# Schematic.net
KiCad netlist of a schematic drawn in EAGLE
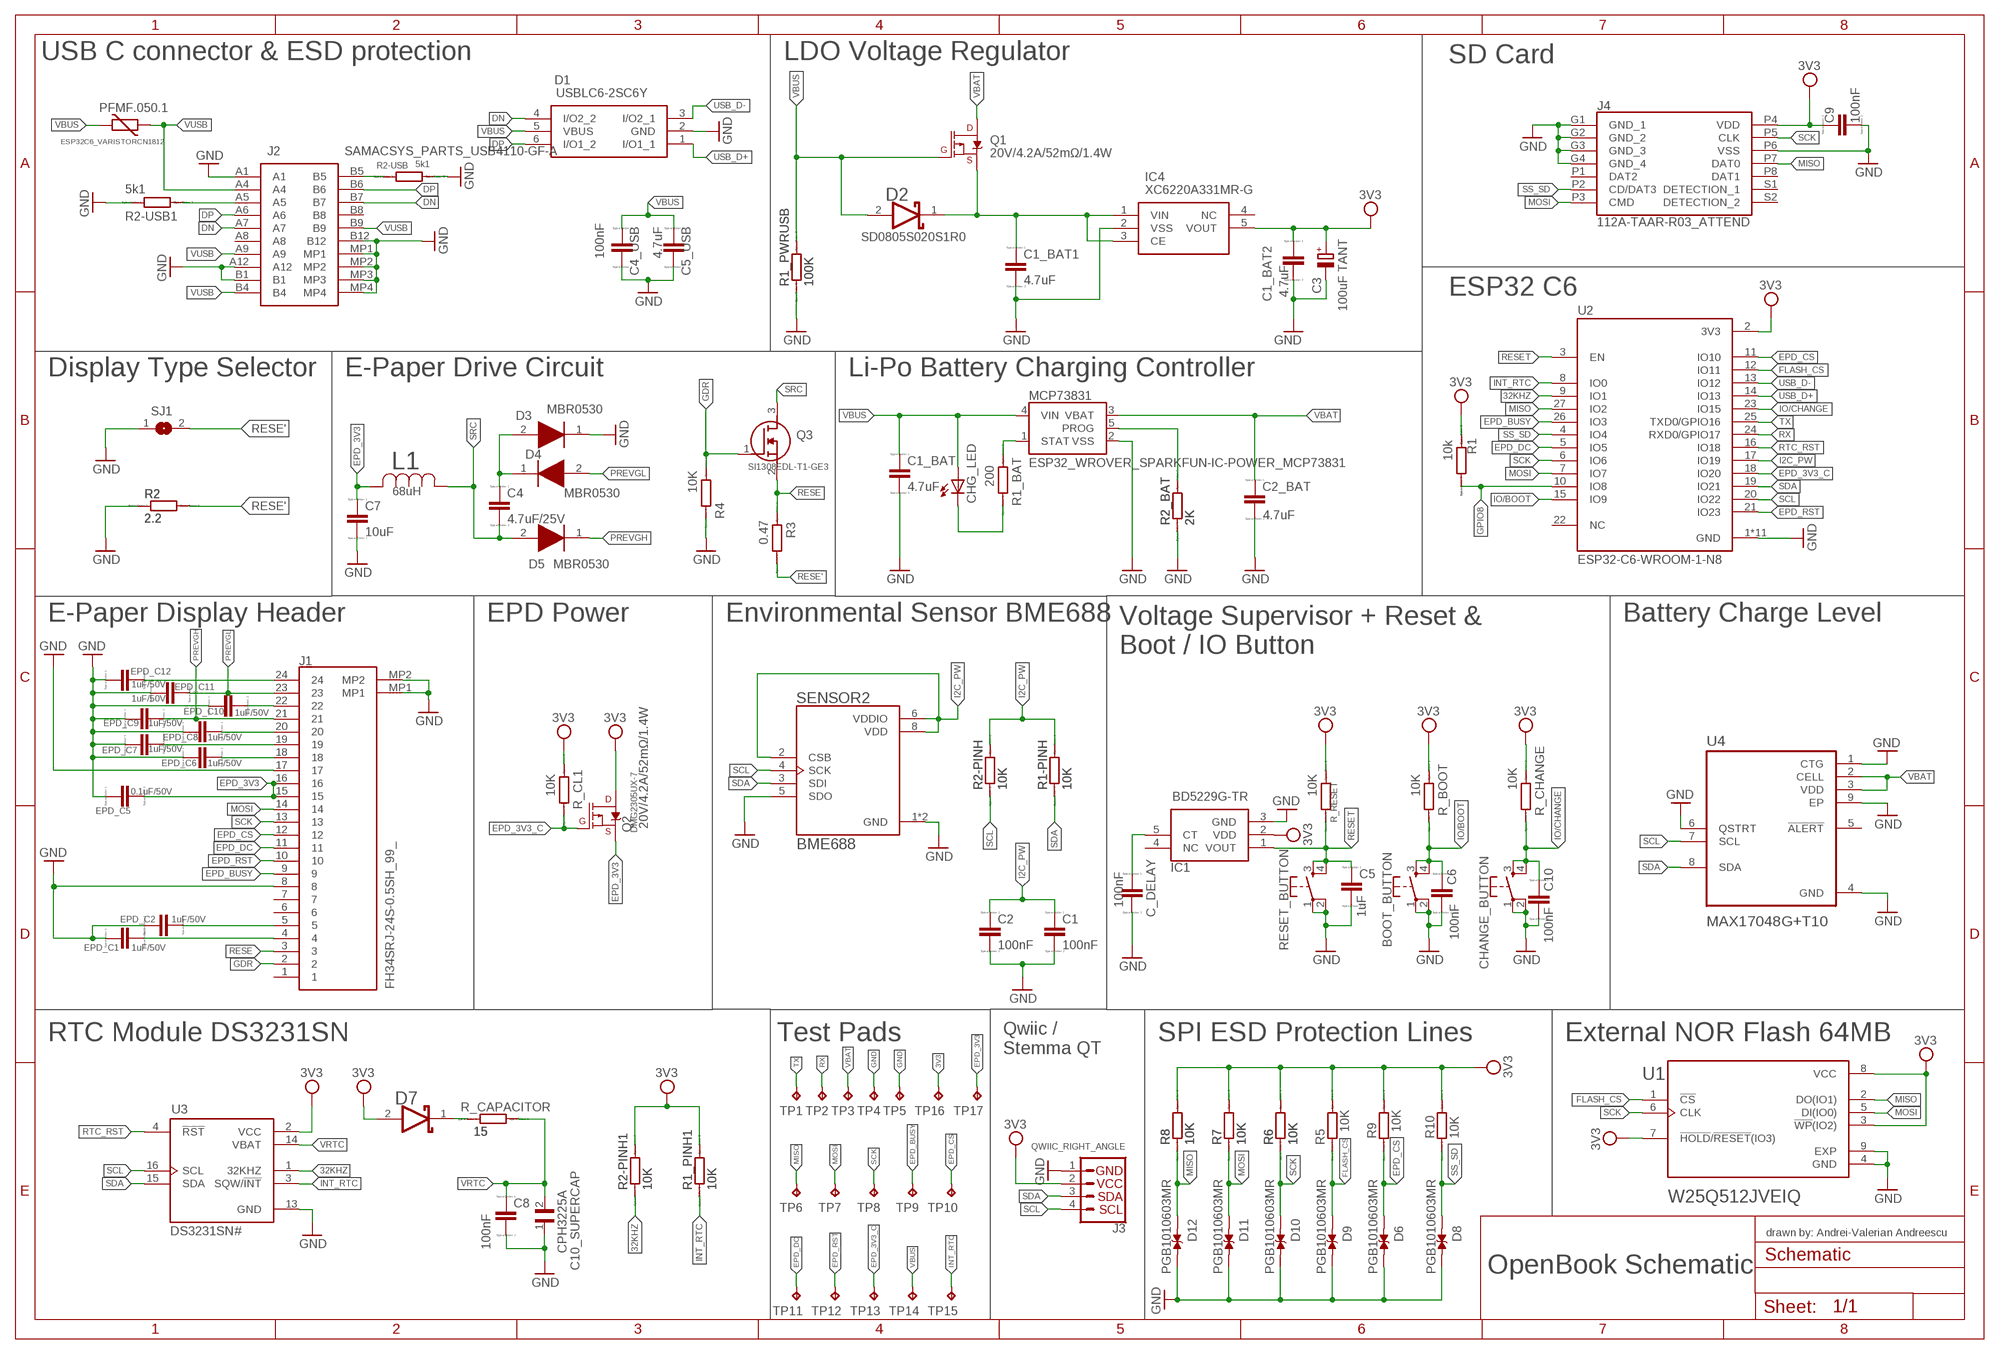
[diagram p0: schematic, sheet 1]

(export (version "E")
  (design (tool "Eeschema 10.0.6"))
  (components
    (comp (ref "BOOT_BUTTON")
      (value "BUTTON_CUSYOMV1")
      (footprint "eagle-import:MYBUTTON")
      (libsource (lib "eagle-import") (part "BUTTON_CUSYOMV1"))
    )
    (comp (ref "C1")
      (value "100nF")
      (footprint "eagle-import:ESP32_WROVER_EAGLE-LTSPICE_C0402")
      (libsource (lib "eagle-import") (part "ESP32_WROVER_EAGLE-LTSPICE_CC0402"))
    )
    (comp (ref "C1_BAT")
      (value "4.7uF")
      (footprint "eagle-import:EAGLE-LTSPICE_C0402")
      (libsource (lib "eagle-import") (part "EAGLE-LTSPICE_CC0402"))
    )
    (comp (ref "C1_BAT1")
      (value "4.7uF")
      (footprint "eagle-import:EAGLE-LTSPICE_C0402")
      (libsource (lib "eagle-import") (part "EAGLE-LTSPICE_CC0402"))
    )
    (comp (ref "C1_BAT2")
      (value "4.7uF")
      (footprint "eagle-import:EAGLE-LTSPICE_C0402")
      (libsource (lib "eagle-import") (part "EAGLE-LTSPICE_CC0402"))
    )
    (comp (ref "C2")
      (value "100nF")
      (footprint "eagle-import:ESP32_WROVER_EAGLE-LTSPICE_C0402")
      (libsource (lib "eagle-import") (part "ESP32_WROVER_EAGLE-LTSPICE_CC0402"))
    )
    (comp (ref "C2_BAT")
      (value "4.7uF")
      (footprint "eagle-import:EAGLE-LTSPICE_C0402")
      (libsource (lib "eagle-import") (part "EAGLE-LTSPICE_CC0402"))
    )
    (comp (ref "C3")
      (value "100uF TANT")
      (footprint "eagle-import:RCL_CT3528")
      (libsource (lib "eagle-import") (part "RCL_CPOL-EUCT3528"))
    )
    (comp (ref "C4")
      (value "4.7uF/25V")
      (footprint "eagle-import:ESP32_WROVER_EAGLE-LTSPICE_C0402")
      (libsource (lib "eagle-import") (part "ESP32_WROVER_EAGLE-LTSPICE_CC0402"))
    )
    (comp (ref "C4_USB")
      (value "100nF")
      (footprint "eagle-import:EAGLE-LTSPICE_C0402")
      (libsource (lib "eagle-import") (part "EAGLE-LTSPICE_CC0402"))
    )
    (comp (ref "C5")
      (value "1uF")
      (footprint "eagle-import:ESP32_WROVER_EAGLE-LTSPICE_C0402")
      (libsource (lib "eagle-import") (part "ESP32_WROVER_EAGLE-LTSPICE_CC0402"))
    )
    (comp (ref "C5_USB")
      (value "4.7uF")
      (footprint "eagle-import:EAGLE-LTSPICE_C0402")
      (libsource (lib "eagle-import") (part "EAGLE-LTSPICE_CC0402"))
    )
    (comp (ref "C6")
      (value "100nF")
      (footprint "eagle-import:ESP32_WROVER_EAGLE-LTSPICE_C0402")
      (libsource (lib "eagle-import") (part "ESP32_WROVER_EAGLE-LTSPICE_CC0402"))
    )
    (comp (ref "C7")
      (value "10uF")
      (footprint "eagle-import:ESP32_WROVER_EAGLE-LTSPICE_C0402")
      (libsource (lib "eagle-import") (part "ESP32_WROVER_EAGLE-LTSPICE_CC0402"))
    )
    (comp (ref "C8")
      (value "100nF")
      (footprint "eagle-import:ESP32_WROVER_EAGLE-LTSPICE_C0402")
      (libsource (lib "eagle-import") (part "ESP32_WROVER_EAGLE-LTSPICE_CC0402"))
    )
    (comp (ref "C9")
      (value "100nF")
      (footprint "eagle-import:EAGLE-LTSPICE_C0402")
      (libsource (lib "eagle-import") (part "EAGLE-LTSPICE_CC0402"))
    )
    (comp (ref "C10")
      (value "100nF")
      (footprint "eagle-import:ESP32_WROVER_EAGLE-LTSPICE_C0402")
      (libsource (lib "eagle-import") (part "ESP32_WROVER_EAGLE-LTSPICE_CC0402"))
    )
    (comp (ref "C10_SUPERCAP")
      (value "CPH3225A")
      (footprint "eagle-import:CAPCP3225X100N")
      (fields (field (name "MF") "Seiko Instruments"))
      (libsource (lib "eagle-import") (part "CPH3225A"))
    )
    (comp (ref "CHANGE_BUTTON")
      (value "BUTTON_CUSYOMV1")
      (footprint "eagle-import:MYBUTTON")
      (libsource (lib "eagle-import") (part "BUTTON_CUSYOMV1"))
    )
    (comp (ref "CHG_LED")
      (value "ADAFRUIT_LEDCHIP-LED0603")
      (footprint "eagle-import:ADAFRUIT_CHIP-LED0603")
      (libsource (lib "eagle-import") (part "ADAFRUIT_LEDCHIP-LED0603"))
    )
    (comp (ref "C_DELAY")
      (value "100nF")
      (footprint "eagle-import:ESP32_WROVER_EAGLE-LTSPICE_C0402")
      (libsource (lib "eagle-import") (part "ESP32_WROVER_EAGLE-LTSPICE_CC0402"))
    )
    (comp (ref "D1")
      (value "USBLC6-2SC6Y")
      (footprint "eagle-import:SOIC127P1032X265-16N")
      (fields (field (name "MF") "STMicroelectronics"))
      (libsource (lib "eagle-import") (part "USBLC6-2SC6Y"))
    )
    (comp (ref "D2")
      (value "SD0805S020S1R0")
      (footprint "eagle-import:ESP32_WROVER_AVX---SD0805S020S1R0_AVX_SD0805S020S1R0_0")
      (fields
        (field (name "DIGIKEY_PART_NUMBER") "478-7800-1-ND")
        (field (name "MF") "AVX")
        (field (name "MOUSER_PART_NUMBER") "581-SD0805S020S1R0")
        (field (name "VALUE_DISPLAY") "SD0805S020S1R0")
      )
      (libsource (lib "eagle-import") (part "ESP32_WROVER_AVX---SD0805S020S1R0_AVX_SD0805S020S1R0_0_0AVX_SD0805S020S1R0_0_0"))
    )
    (comp (ref "D3")
      (value "MBR0530")
      (footprint "eagle-import:SOD3716X135N")
      (fields (field (name "MF") "ON Semiconductor"))
      (libsource (lib "eagle-import") (part "MBR0530"))
    )
    (comp (ref "D4")
      (value "MBR0530")
      (footprint "eagle-import:SOD3716X135N")
      (fields (field (name "MF") "ON Semiconductor"))
      (libsource (lib "eagle-import") (part "MBR0530"))
    )
    (comp (ref "D5")
      (value "MBR0530")
      (footprint "eagle-import:SOD3716X135N")
      (fields (field (name "MF") "ON Semiconductor"))
      (libsource (lib "eagle-import") (part "MBR0530"))
    )
    (comp (ref "D6")
      (value "PGB1010603MR")
      (footprint "eagle-import:DIOC1608X36N")
      (fields (field (name "MF") "Littelfuse Inc."))
      (libsource (lib "eagle-import") (part "PGB1010603MR"))
    )
    (comp (ref "D7")
      (value "ESP32_WROVER_AVX---SD0805S020S1R0_AVX_SD0805S020S1R0_0_0AVX_SD0805S020S1R0_0_0")
      (footprint "eagle-import:ESP32_WROVER_AVX---SD0805S020S1R0_AVX_SD0805S020S1R0_0")
      (fields
        (field (name "DIGIKEY_PART_NUMBER") "478-7800-1-ND")
        (field (name "MF") "AVX")
        (field (name "MOUSER_PART_NUMBER") "581-SD0805S020S1R0")
      )
      (libsource (lib "eagle-import") (part "ESP32_WROVER_AVX---SD0805S020S1R0_AVX_SD0805S020S1R0_0_0AVX_SD0805S020S1R0_0_0"))
    )
    (comp (ref "D8")
      (value "PGB1010603MR")
      (footprint "eagle-import:DIOC1608X36N")
      (fields (field (name "MF") "Littelfuse Inc."))
      (libsource (lib "eagle-import") (part "PGB1010603MR"))
    )
    (comp (ref "D9")
      (value "PGB1010603MR")
      (footprint "eagle-import:DIOC1608X36N")
      (fields (field (name "MF") "Littelfuse Inc."))
      (libsource (lib "eagle-import") (part "PGB1010603MR"))
    )
    (comp (ref "D10")
      (value "PGB1010603MR")
      (footprint "eagle-import:DIOC1608X36N")
      (fields (field (name "MF") "Littelfuse Inc."))
      (libsource (lib "eagle-import") (part "PGB1010603MR"))
    )
    (comp (ref "D11")
      (value "PGB1010603MR")
      (footprint "eagle-import:DIOC1608X36N")
      (fields (field (name "MF") "Littelfuse Inc."))
      (libsource (lib "eagle-import") (part "PGB1010603MR"))
    )
    (comp (ref "D12")
      (value "PGB1010603MR")
      (footprint "eagle-import:DIOC1608X36N")
      (fields (field (name "MF") "Littelfuse Inc."))
      (libsource (lib "eagle-import") (part "PGB1010603MR"))
    )
    (comp (ref "EPD_C1")
      (value "1uF/50V")
      (footprint "eagle-import:ESP32_WROVER_EAGLE-LTSPICE_C0402")
      (libsource (lib "eagle-import") (part "ESP32_WROVER_EAGLE-LTSPICE_CC0402"))
    )
    (comp (ref "EPD_C2")
      (value "1uF/50V")
      (footprint "eagle-import:ESP32_WROVER_EAGLE-LTSPICE_C0402")
      (libsource (lib "eagle-import") (part "ESP32_WROVER_EAGLE-LTSPICE_CC0402"))
    )
    (comp (ref "EPD_C5")
      (value "0.1uF/50V")
      (footprint "eagle-import:ESP32_WROVER_EAGLE-LTSPICE_C0402")
      (libsource (lib "eagle-import") (part "ESP32_WROVER_EAGLE-LTSPICE_CC0402"))
    )
    (comp (ref "EPD_C6")
      (value "1uF/50V")
      (footprint "eagle-import:ESP32_WROVER_EAGLE-LTSPICE_C0402")
      (libsource (lib "eagle-import") (part "ESP32_WROVER_EAGLE-LTSPICE_CC0402"))
    )
    (comp (ref "EPD_C7")
      (value "1uF/50V")
      (footprint "eagle-import:ESP32_WROVER_EAGLE-LTSPICE_C0402")
      (libsource (lib "eagle-import") (part "ESP32_WROVER_EAGLE-LTSPICE_CC0402"))
    )
    (comp (ref "EPD_C8")
      (value "1uF/50V")
      (footprint "eagle-import:ESP32_WROVER_EAGLE-LTSPICE_C0402")
      (libsource (lib "eagle-import") (part "ESP32_WROVER_EAGLE-LTSPICE_CC0402"))
    )
    (comp (ref "EPD_C9")
      (value "1uF/50V")
      (footprint "eagle-import:ESP32_WROVER_EAGLE-LTSPICE_C0402")
      (libsource (lib "eagle-import") (part "ESP32_WROVER_EAGLE-LTSPICE_CC0402"))
    )
    (comp (ref "EPD_C10")
      (value "1uF/50V")
      (footprint "eagle-import:ESP32_WROVER_EAGLE-LTSPICE_C0402")
      (libsource (lib "eagle-import") (part "ESP32_WROVER_EAGLE-LTSPICE_CC0402"))
    )
    (comp (ref "EPD_C11")
      (value "1uF/50V")
      (footprint "eagle-import:ESP32_WROVER_EAGLE-LTSPICE_C0402")
      (libsource (lib "eagle-import") (part "ESP32_WROVER_EAGLE-LTSPICE_CC0402"))
    )
    (comp (ref "EPD_C12")
      (value "1uF/50V")
      (footprint "eagle-import:ESP32_WROVER_EAGLE-LTSPICE_C0402")
      (libsource (lib "eagle-import") (part "ESP32_WROVER_EAGLE-LTSPICE_CC0402"))
    )
    (comp (ref "IC1")
      (value "BD5229G-TR")
      (footprint "eagle-import:SOT95P280X120-5N")
      (fields (field (name "MOUSER_PART_NUMBER") "755-BD5229G-TR"))
      (libsource (lib "eagle-import") (part "BD5229G-TR"))
    )
    (comp (ref "IC4")
      (value "XC6220A331MR-G")
      (footprint "eagle-import:SOT95P280X120-5N")
      (fields (field (name "MOUSER_PART_NUMBER") "865-XC6220A331MR-G"))
      (libsource (lib "eagle-import") (part "XC6220A331MR-G"))
    )
    (comp (ref "J1")
      (value "FH34SRJ-24S-0.5SH_99_")
      (footprint "eagle-import:FH34SRJ24S05SH99")
      (fields
        (field (name "MANUFACTURER_PART_NUMBER") "FH34SRJ-24S-0.5SH(99)")
        (field (name "MOUSER_PART_NUMBER") "798-FH34SRJ24S05SH99")
      )
      (libsource (lib "eagle-import") (part "FH34SRJ-24S-0.5SH_99_"))
    )
    (comp (ref "J2")
      (value "SAMACSYS_PARTS_USB4110-GF-A")
      (footprint "eagle-import:SAMACSYS_PARTS_USB4110GFA")
      (fields
        (field (name "MANUFACTURER_PART_NUMBER") "USB4110-GF-A")
        (field (name "MOUSER_PART_NUMBER") "640-USB4110-GF-A")
      )
      (libsource (lib "eagle-import") (part "SAMACSYS_PARTS_USB4110-GF-A"))
    )
    (comp (ref "J3")
      (value "QWIIC_RIGHT_ANGLE")
      (footprint "eagle-import:JST04_1MM_RA")
      (libsource (lib "eagle-import") (part "QWIIC_CONNECTORJS-1MM"))
    )
    (comp (ref "J4")
      (value "112A-TAAR-R03_ATTEND")
      (footprint "eagle-import:112ATAARR03ATTEND")
      (fields (field (name "MANUFACTURER_PART_NUMBER") "112A-TAAR-R03 ATTEND"))
      (libsource (lib "eagle-import") (part "112A-TAAR-R03_ATTEND"))
    )
    (comp (ref "L1")
      (value "68uH")
      (footprint "eagle-import:IND_4828-WE-TPC_WRE")
      (fields
        (field (name "MANUFACTURER_PART_NUMBER") "744043680")
        (field (name "COPYRIGHT") "Copyright (C) 2024 Ultra Librarian. All rights reserved.")
      )
      (libsource (lib "eagle-import") (part "744043680IND_4828-WE-TPC_WRE"))
    )
    (comp (ref "MCP73831")
      (value "ESP32_WROVER_SPARKFUN-IC-POWER_MCP73831")
      (footprint "eagle-import:ESP32_WROVER_SPARKFUN-IC-POWER_SOT23-5")
      (libsource (lib "eagle-import") (part "ESP32_WROVER_SPARKFUN-IC-POWER_MCP73831"))
    )
    (comp (ref "PFMF.050.1")
      (value "ESP32C6_VARISTORCN1812")
      (footprint "eagle-import:ESP32C6_VARISTOR_CT_CN1812")
      (libsource (lib "eagle-import") (part "ESP32C6_VARISTORCN1812"))
    )
    (comp (ref "Q1")
      (value "20V/4.2A/52mΩ/1.4W")
      (footprint "eagle-import:ESP32_WROVER_SPARKFUN-DISCRETESEMI_SOT23-3")
      (libsource (lib "eagle-import") (part "ESP32_WROVER_SPARKFUN-DISCRETESEMI_MOSFET_PCH-DMG2305UX-7"))
    )
    (comp (ref "Q2")
      (value "20V/4.2A/52mΩ/1.4W")
      (footprint "eagle-import:ESP32_WROVER_SPARKFUN-DISCRETESEMI_SOT23-3")
      (fields (field (name "ATRIBUT") "DMG2305UX-7"))
      (libsource (lib "eagle-import") (part "ESP32_WROVER_SPARKFUN-DISCRETESEMI_MOSFET_PCH-DMG2305UX-7"))
    )
    (comp (ref "Q3")
      (value "SI1308EDL-T1-GE3")
      (footprint "eagle-import:SOT65P210X110-3N")
      (fields (field (name "MF") "Vishay Siliconix"))
      (libsource (lib "eagle-import") (part "SI1308EDL-T1-GE3"))
    )
    (comp (ref "R1")
      (value "10k")
      (footprint "eagle-import:ESP32_WROVER_EAGLE-LTSPICE_R0402")
      (libsource (lib "eagle-import") (part "ESP32_WROVER_EAGLE-LTSPICE_RR0402"))
    )
    (comp (ref "R1-PINH")
      (value "10K")
      (footprint "eagle-import:ESP32_WROVER_EAGLE-LTSPICE_R0402")
      (libsource (lib "eagle-import") (part "ESP32_WROVER_EAGLE-LTSPICE_RR0402"))
    )
    (comp (ref "R1_BAT")
      (value "200")
      (footprint "eagle-import:ESP32_WROVER_EAGLE-LTSPICE_R0402")
      (libsource (lib "eagle-import") (part "ESP32_WROVER_EAGLE-LTSPICE_RR0402"))
    )
    (comp (ref "R1_PINH1")
      (value "10K")
      (footprint "eagle-import:ESP32_WROVER_EAGLE-LTSPICE_R0402")
      (libsource (lib "eagle-import") (part "ESP32_WROVER_EAGLE-LTSPICE_RR0402"))
    )
    (comp (ref "R1_PWRUSB")
      (value "100K")
      (footprint "eagle-import:ESP32_WROVER_EAGLE-LTSPICE_R0402")
      (libsource (lib "eagle-import") (part "ESP32_WROVER_EAGLE-LTSPICE_RR0402"))
    )
    (comp (ref "R2")
      (value "2.2")
      (footprint "eagle-import:ESP32_WROVER_EAGLE-LTSPICE_R0402")
      (libsource (lib "eagle-import") (part "ESP32_WROVER_EAGLE-LTSPICE_RR0402"))
    )
    (comp (ref "R2-PINH")
      (value "10K")
      (footprint "eagle-import:ESP32_WROVER_EAGLE-LTSPICE_R0402")
      (libsource (lib "eagle-import") (part "ESP32_WROVER_EAGLE-LTSPICE_RR0402"))
    )
    (comp (ref "R2-PINH1")
      (value "10K")
      (footprint "eagle-import:ESP32_WROVER_EAGLE-LTSPICE_R0402")
      (libsource (lib "eagle-import") (part "ESP32_WROVER_EAGLE-LTSPICE_RR0402"))
    )
    (comp (ref "R2-USB")
      (value "5k1")
      (footprint "eagle-import:ESP32_WROVER_EAGLE-LTSPICE_R0402")
      (libsource (lib "eagle-import") (part "ESP32_WROVER_EAGLE-LTSPICE_RR0402"))
    )
    (comp (ref "R2-USB1")
      (value "5k1")
      (footprint "eagle-import:ESP32_WROVER_EAGLE-LTSPICE_R0402")
      (libsource (lib "eagle-import") (part "ESP32_WROVER_EAGLE-LTSPICE_RR0402"))
    )
    (comp (ref "R2_BAT")
      (value "2K")
      (footprint "eagle-import:ESP32_WROVER_EAGLE-LTSPICE_R0402")
      (libsource (lib "eagle-import") (part "ESP32_WROVER_EAGLE-LTSPICE_RR0402"))
    )
    (comp (ref "R3")
      (value "0.47")
      (footprint "eagle-import:ESP32_WROVER_EAGLE-LTSPICE_R0402")
      (libsource (lib "eagle-import") (part "ESP32_WROVER_EAGLE-LTSPICE_RR0402"))
    )
    (comp (ref "R4")
      (value "10K")
      (footprint "eagle-import:ESP32_WROVER_EAGLE-LTSPICE_R0402")
      (libsource (lib "eagle-import") (part "ESP32_WROVER_EAGLE-LTSPICE_RR0402"))
    )
    (comp (ref "R5")
      (value "10K")
      (footprint "eagle-import:ESP32_WROVER_EAGLE-LTSPICE_R0402")
      (libsource (lib "eagle-import") (part "ESP32_WROVER_EAGLE-LTSPICE_RR0402"))
    )
    (comp (ref "R6")
      (value "10K")
      (footprint "eagle-import:ESP32_WROVER_EAGLE-LTSPICE_R0402")
      (libsource (lib "eagle-import") (part "ESP32_WROVER_EAGLE-LTSPICE_RR0402"))
    )
    (comp (ref "R7")
      (value "10K")
      (footprint "eagle-import:ESP32_WROVER_EAGLE-LTSPICE_R0402")
      (libsource (lib "eagle-import") (part "ESP32_WROVER_EAGLE-LTSPICE_RR0402"))
    )
    (comp (ref "R8")
      (value "10K")
      (footprint "eagle-import:ESP32_WROVER_EAGLE-LTSPICE_R0402")
      (libsource (lib "eagle-import") (part "ESP32_WROVER_EAGLE-LTSPICE_RR0402"))
    )
    (comp (ref "R9")
      (value "10K")
      (footprint "eagle-import:ESP32_WROVER_EAGLE-LTSPICE_R0402")
      (libsource (lib "eagle-import") (part "ESP32_WROVER_EAGLE-LTSPICE_RR0402"))
    )
    (comp (ref "R10")
      (value "10K")
      (footprint "eagle-import:ESP32_WROVER_EAGLE-LTSPICE_R0402")
      (libsource (lib "eagle-import") (part "ESP32_WROVER_EAGLE-LTSPICE_RR0402"))
    )
    (comp (ref "RESET_BUTTON")
      (value "BUTTON_CUSYOMV1")
      (footprint "eagle-import:MYBUTTON")
      (libsource (lib "eagle-import") (part "BUTTON_CUSYOMV1"))
    )
    (comp (ref "R_BOOT")
      (value "10K")
      (footprint "eagle-import:ESP32_WROVER_EAGLE-LTSPICE_R0402")
      (libsource (lib "eagle-import") (part "ESP32_WROVER_EAGLE-LTSPICE_RR0402"))
    )
    (comp (ref "R_CAPACITOR")
      (value "15")
      (footprint "eagle-import:ESP32_WROVER_EAGLE-LTSPICE_R0402")
      (libsource (lib "eagle-import") (part "ESP32_WROVER_EAGLE-LTSPICE_RR0402"))
    )
    (comp (ref "R_CHANGE")
      (value "10K")
      (footprint "eagle-import:ESP32_WROVER_EAGLE-LTSPICE_R0402")
      (libsource (lib "eagle-import") (part "ESP32_WROVER_EAGLE-LTSPICE_RR0402"))
    )
    (comp (ref "R_CL1")
      (value "10K")
      (footprint "eagle-import:ESP32_WROVER_EAGLE-LTSPICE_R0402")
      (libsource (lib "eagle-import") (part "ESP32_WROVER_EAGLE-LTSPICE_RR0402"))
    )
    (comp (ref "R_RESET")
      (value "10K")
      (footprint "eagle-import:ESP32_WROVER_EAGLE-LTSPICE_R0402")
      (libsource (lib "eagle-import") (part "ESP32_WROVER_EAGLE-LTSPICE_RR0402"))
    )
    (comp (ref "SENSOR2")
      (value "BME688")
      (footprint "eagle-import:ESP32_WROVER_BME680_PSON80P300X300X100-8N")
      (fields (field (name "MF") "Bosch Sensortec") (field (name "MP") "BME680"))
      (libsource (lib "eagle-import") (part "ESP32_WROVER_BME680_BME680"))
    )
    (comp (ref "SJ1") (value "SJ") (footprint "eagle-import:SJ") (libsource (lib "eagle-import") (part "SJ")))
    (comp (ref "TP1")
      (value "TPTP20R")
      (footprint "eagle-import:TP20R")
      (libsource (lib "eagle-import") (part "TPTP20R"))
    )
    (comp (ref "TP2")
      (value "TPTP20R")
      (footprint "eagle-import:TP20R")
      (libsource (lib "eagle-import") (part "TPTP20R"))
    )
    (comp (ref "TP3")
      (value "TPTP20R")
      (footprint "eagle-import:TP20R")
      (libsource (lib "eagle-import") (part "TPTP20R"))
    )
    (comp (ref "TP4")
      (value "TPTP20R")
      (footprint "eagle-import:TP20R")
      (libsource (lib "eagle-import") (part "TPTP20R"))
    )
    (comp (ref "TP5")
      (value "TPTP20R")
      (footprint "eagle-import:TP20R")
      (libsource (lib "eagle-import") (part "TPTP20R"))
    )
    (comp (ref "TP6")
      (value "TPTP20R")
      (footprint "eagle-import:TP20R")
      (libsource (lib "eagle-import") (part "TPTP20R"))
    )
    (comp (ref "TP7")
      (value "TPTP20R")
      (footprint "eagle-import:TP20R")
      (libsource (lib "eagle-import") (part "TPTP20R"))
    )
    (comp (ref "TP8")
      (value "TPTP20R")
      (footprint "eagle-import:TP20R")
      (libsource (lib "eagle-import") (part "TPTP20R"))
    )
    (comp (ref "TP9")
      (value "TPTP20R")
      (footprint "eagle-import:TP20R")
      (libsource (lib "eagle-import") (part "TPTP20R"))
    )
    (comp (ref "TP10")
      (value "TPTP20R")
      (footprint "eagle-import:TP20R")
      (libsource (lib "eagle-import") (part "TPTP20R"))
    )
    (comp (ref "TP11")
      (value "TPTP20R")
      (footprint "eagle-import:TP20R")
      (libsource (lib "eagle-import") (part "TPTP20R"))
    )
    (comp (ref "TP12")
      (value "TPTP20R")
      (footprint "eagle-import:TP20R")
      (libsource (lib "eagle-import") (part "TPTP20R"))
    )
    (comp (ref "TP13")
      (value "TPTP20R")
      (footprint "eagle-import:TP20R")
      (libsource (lib "eagle-import") (part "TPTP20R"))
    )
    (comp (ref "TP14")
      (value "TPTP20R")
      (footprint "eagle-import:TP20R")
      (libsource (lib "eagle-import") (part "TPTP20R"))
    )
    (comp (ref "TP15")
      (value "TPTP20R")
      (footprint "eagle-import:TP20R")
      (libsource (lib "eagle-import") (part "TPTP20R"))
    )
    (comp (ref "TP16")
      (value "TPTP20R")
      (footprint "eagle-import:TP20R")
      (libsource (lib "eagle-import") (part "TPTP20R"))
    )
    (comp (ref "TP17")
      (value "TPTP20R")
      (footprint "eagle-import:TP20R")
      (libsource (lib "eagle-import") (part "TPTP20R"))
    )
    (comp (ref "U1")
      (value "W25Q512JVEIQ")
      (footprint "eagle-import:SON127P600X800X80-9N")
      (fields (field (name "MF") "Winbond Electronics"))
      (libsource (lib "eagle-import") (part "W25Q512JVEIQ"))
    )
    (comp (ref "U2")
      (value "ESP32-C6-WROOM-1-N8")
      (footprint "eagle-import:XCVR_ESP32-C6-WROOM-1-N8")
      (fields (field (name "MF") "Espressif Systems"))
      (libsource (lib "eagle-import") (part "ESP32-C6-WROOM-1-N8"))
    )
    (comp (ref "U3")
      (value "DS3231SN#")
      (footprint "eagle-import:SOIC127P1032X265-16N")
      (fields (field (name "MF") "Analog Devices"))
      (libsource (lib "eagle-import") (part "DS3231SN#"))
    )
    (comp (ref "U4")
      (value "MAX17048G+T10")
      (footprint "eagle-import:SON50P200X200X80-9N")
      (fields (field (name "MF") "Analog Devices"))
      (libsource (lib "eagle-import") (part "MAX17048G+T10"))
    )
  )
  (nets
    (net (code "1") (name "3V3") (class "Default")
      (node (ref "C1_BAT2") (pin "1") (pinfunction "1_1") (pintype "passive"))
      (node (ref "C3") (pin "+") (pinfunction "+_+") (pintype "passive"))
      (node (ref "C9") (pin "2") (pinfunction "2_2") (pintype "passive"))
      (node (ref "D7") (pin "2") (pinfunction "ANODE_2") (pintype "bidirectional"))
      (node (ref "IC1") (pin "2") (pinfunction "VDD_2") (pintype "bidirectional"))
      (node (ref "IC4") (pin "5") (pinfunction "VOUT_5") (pintype "bidirectional"))
      (node (ref "J3") (pin "2") (pinfunction "2_2") (pintype "power_in"))
      (node (ref "J4") (pin "P4") (pinfunction "VDD_P4") (pintype "bidirectional"))
      (node (ref "Q2") (pin "3") (pinfunction "D_3") (pintype "bidirectional"))
      (node (ref "R1") (pin "2") (pinfunction "2_2") (pintype "passive"))
      (node (ref "R10") (pin "2") (pinfunction "2_2") (pintype "passive"))
      (node (ref "R1_PINH1") (pin "2") (pinfunction "2_2") (pintype "passive"))
      (node (ref "R2-PINH1") (pin "2") (pinfunction "2_2") (pintype "passive"))
      (node (ref "R5") (pin "2") (pinfunction "2_2") (pintype "passive"))
      (node (ref "R6") (pin "2") (pinfunction "2_2") (pintype "passive"))
      (node (ref "R7") (pin "2") (pinfunction "2_2") (pintype "passive"))
      (node (ref "R8") (pin "2") (pinfunction "2_2") (pintype "passive"))
      (node (ref "R9") (pin "2") (pinfunction "2_2") (pintype "passive"))
      (node (ref "R_BOOT") (pin "2") (pinfunction "2_2") (pintype "passive"))
      (node (ref "R_CHANGE") (pin "2") (pinfunction "2_2") (pintype "passive"))
      (node (ref "R_CL1") (pin "2") (pinfunction "2_2") (pintype "passive"))
      (node (ref "R_RESET") (pin "2") (pinfunction "2_2") (pintype "passive"))
      (node (ref "TP16") (pin "TP") (pinfunction "TP_TP") (pintype "input"))
      (node (ref "U1") (pin "3") (pinfunction "~{WP}(IO2)_3") (pintype "bidirectional"))
      (node (ref "U1") (pin "7") (pinfunction "~{HOLD}/~{RESET}(IO3)_7") (pintype "bidirectional"))
      (node (ref "U1") (pin "8") (pinfunction "VCC_8") (pintype "power_in"))
      (node (ref "U2") (pin "2") (pinfunction "3V3_2") (pintype "power_in"))
      (node (ref "U3") (pin "2") (pinfunction "VCC_2") (pintype "power_in"))
    )
    (net (code "2") (name "32KHZ") (class "Default")
      (node (ref "R2-PINH1") (pin "1") (pinfunction "1_1") (pintype "passive"))
      (node (ref "U2") (pin "9") (pinfunction "IO1_9") (pintype "bidirectional"))
      (node (ref "U3") (pin "1") (pinfunction "32KHZ_1") (pintype "output"))
    )
    (net (code "3") (name "DN") (class "Default")
      (node (ref "D1") (pin "4") (pinfunction "I/O2_2_4") (pintype "bidirectional"))
      (node (ref "J2") (pin "A7") (pinfunction "A7_A7") (pintype "bidirectional"))
      (node (ref "J2") (pin "B7") (pinfunction "B7_B7") (pintype "bidirectional"))
    )
    (net (code "4") (name "DP") (class "Default")
      (node (ref "D1") (pin "6") (pinfunction "I/O1_2_6") (pintype "bidirectional"))
      (node (ref "J2") (pin "A6") (pinfunction "A6_A6") (pintype "bidirectional"))
      (node (ref "J2") (pin "B6") (pinfunction "B6_B6") (pintype "bidirectional"))
    )
    (net (code "5") (name "EPD_3V3") (class "Default")
      (node (ref "C7") (pin "1") (pinfunction "1_1") (pintype "passive"))
      (node (ref "EPD_C5") (pin "2") (pinfunction "2_2") (pintype "passive"))
      (node (ref "J1") (pin "15") (pinfunction "15_15") (pintype "bidirectional"))
      (node (ref "J1") (pin "16") (pinfunction "16_16") (pintype "bidirectional"))
      (node (ref "L1") (pin "2") (pinfunction "2_2") (pintype "passive"))
      (node (ref "Q2") (pin "2") (pinfunction "S_2") (pintype "bidirectional"))
      (node (ref "TP17") (pin "TP") (pinfunction "TP_TP") (pintype "input"))
    )
    (net (code "6") (name "EPD_3V3_C") (class "Default")
      (node (ref "Q2") (pin "1") (pinfunction "G_1") (pintype "bidirectional"))
      (node (ref "R_CL1") (pin "1") (pinfunction "1_1") (pintype "passive"))
      (node (ref "TP13") (pin "TP") (pinfunction "TP_TP") (pintype "input"))
      (node (ref "U2") (pin "18") (pinfunction "IO20_18") (pintype "bidirectional"))
    )
    (net (code "7") (name "EPD_BUSY") (class "Default")
      (node (ref "J1") (pin "9") (pinfunction "9_9") (pintype "bidirectional"))
      (node (ref "TP9") (pin "TP") (pinfunction "TP_TP") (pintype "input"))
      (node (ref "U2") (pin "26") (pinfunction "IO3_26") (pintype "bidirectional"))
    )
    (net (code "8") (name "EPD_CS") (class "Default")
      (node (ref "D6") (pin "2") (pinfunction "2_2") (pintype "passive"))
      (node (ref "J1") (pin "12") (pinfunction "12_12") (pintype "bidirectional"))
      (node (ref "R9") (pin "1") (pinfunction "1_1") (pintype "passive"))
      (node (ref "TP10") (pin "TP") (pinfunction "TP_TP") (pintype "input"))
      (node (ref "U2") (pin "11") (pinfunction "IO10_11") (pintype "bidirectional"))
    )
    (net (code "9") (name "EPD_DC") (class "Default")
      (node (ref "J1") (pin "11") (pinfunction "11_11") (pintype "bidirectional"))
      (node (ref "TP11") (pin "TP") (pinfunction "TP_TP") (pintype "input"))
      (node (ref "U2") (pin "5") (pinfunction "IO5_5") (pintype "bidirectional"))
    )
    (net (code "10") (name "EPD_RST") (class "Default")
      (node (ref "J1") (pin "10") (pinfunction "10_10") (pintype "bidirectional"))
      (node (ref "TP12") (pin "TP") (pinfunction "TP_TP") (pintype "input"))
      (node (ref "U2") (pin "21") (pinfunction "IO23_21") (pintype "bidirectional"))
    )
    (net (code "11") (name "FLASH_CS") (class "Default")
      (node (ref "D9") (pin "2") (pinfunction "2_2") (pintype "passive"))
      (node (ref "R5") (pin "1") (pinfunction "1_1") (pintype "passive"))
      (node (ref "U1") (pin "1") (pinfunction "~{CS}_1") (pintype "input"))
      (node (ref "U2") (pin "12") (pinfunction "IO11_12") (pintype "bidirectional"))
    )
    (net (code "12") (name "GDR") (class "Default")
      (node (ref "J1") (pin "2") (pinfunction "2_2") (pintype "bidirectional"))
      (node (ref "Q3") (pin "1") (pinfunction "G_1") (pintype "bidirectional"))
      (node (ref "R4") (pin "2") (pinfunction "2_2") (pintype "passive"))
    )
    (net (code "13") (name "GND") (class "Default")
      (node (ref "BOOT_BUTTON") (pin "1") (pinfunction "1_1") (pintype "passive"))
      (node (ref "BOOT_BUTTON") (pin "2") (pinfunction "2_2") (pintype "passive"))
      (node (ref "C1") (pin "2") (pinfunction "2_2") (pintype "passive"))
      (node (ref "C10") (pin "2") (pinfunction "2_2") (pintype "passive"))
      (node (ref "C10_SUPERCAP") (pin "1") (pinfunction "1_1") (pintype "passive"))
      (node (ref "C1_BAT") (pin "2") (pinfunction "2_2") (pintype "passive"))
      (node (ref "C1_BAT1") (pin "2") (pinfunction "2_2") (pintype "passive"))
      (node (ref "C1_BAT2") (pin "2") (pinfunction "2_2") (pintype "passive"))
      (node (ref "C2") (pin "2") (pinfunction "2_2") (pintype "passive"))
      (node (ref "C2_BAT") (pin "2") (pinfunction "2_2") (pintype "passive"))
      (node (ref "C3") (pin "-") (pinfunction "-_-") (pintype "passive"))
      (node (ref "C4_USB") (pin "2") (pinfunction "2_2") (pintype "passive"))
      (node (ref "C5") (pin "2") (pinfunction "2_2") (pintype "passive"))
      (node (ref "C5_USB") (pin "2") (pinfunction "2_2") (pintype "passive"))
      (node (ref "C6") (pin "2") (pinfunction "2_2") (pintype "passive"))
      (node (ref "C7") (pin "2") (pinfunction "2_2") (pintype "passive"))
      (node (ref "C8") (pin "2") (pinfunction "2_2") (pintype "passive"))
      (node (ref "C9") (pin "1") (pinfunction "1_1") (pintype "passive"))
      (node (ref "CHANGE_BUTTON") (pin "1") (pinfunction "1_1") (pintype "passive"))
      (node (ref "CHANGE_BUTTON") (pin "2") (pinfunction "2_2") (pintype "passive"))
      (node (ref "C_DELAY") (pin "2") (pinfunction "2_2") (pintype "passive"))
      (node (ref "D1") (pin "2") (pinfunction "GND_2") (pintype "bidirectional"))
      (node (ref "D10") (pin "1") (pinfunction "1_1") (pintype "passive"))
      (node (ref "D11") (pin "1") (pinfunction "1_1") (pintype "passive"))
      (node (ref "D12") (pin "1") (pinfunction "1_1") (pintype "passive"))
      (node (ref "D3") (pin "1") (pinfunction "K_1") (pintype "bidirectional"))
      (node (ref "D6") (pin "1") (pinfunction "1_1") (pintype "passive"))
      (node (ref "D8") (pin "1") (pinfunction "1_1") (pintype "passive"))
      (node (ref "D9") (pin "1") (pinfunction "1_1") (pintype "passive"))
      (node (ref "EPD_C1") (pin "1") (pinfunction "1_1") (pintype "passive"))
      (node (ref "EPD_C10") (pin "1") (pinfunction "1_1") (pintype "passive"))
      (node (ref "EPD_C11") (pin "1") (pinfunction "1_1") (pintype "passive"))
      (node (ref "EPD_C12") (pin "1") (pinfunction "1_1") (pintype "passive"))
      (node (ref "EPD_C2") (pin "1") (pinfunction "1_1") (pintype "passive"))
      (node (ref "EPD_C5") (pin "1") (pinfunction "1_1") (pintype "passive"))
      (node (ref "EPD_C6") (pin "1") (pinfunction "1_1") (pintype "passive"))
      (node (ref "EPD_C7") (pin "1") (pinfunction "1_1") (pintype "passive"))
      (node (ref "EPD_C8") (pin "1") (pinfunction "1_1") (pintype "passive"))
      (node (ref "EPD_C9") (pin "1") (pinfunction "1_1") (pintype "passive"))
      (node (ref "IC1") (pin "3") (pinfunction "GND_3") (pintype "bidirectional"))
      (node (ref "IC4") (pin "2") (pinfunction "VSS_2") (pintype "bidirectional"))
      (node (ref "J1") (pin "17") (pinfunction "17_17") (pintype "bidirectional"))
      (node (ref "J1") (pin "8") (pinfunction "8_8") (pintype "bidirectional"))
      (node (ref "J1") (pin "MP1") (pinfunction "MP1_MP1") (pintype "bidirectional"))
      (node (ref "J1") (pin "MP2") (pinfunction "MP2_MP2") (pintype "bidirectional"))
      (node (ref "J2") (pin "A1") (pinfunction "A1_A1") (pintype "bidirectional"))
      (node (ref "J2") (pin "A12") (pinfunction "A12_A12") (pintype "bidirectional"))
      (node (ref "J2") (pin "B1") (pinfunction "B1_B1") (pintype "bidirectional"))
      (node (ref "J2") (pin "B12") (pinfunction "B12_B12") (pintype "bidirectional"))
      (node (ref "J2") (pin "MP1") (pinfunction "MP1_MP1") (pintype "bidirectional"))
      (node (ref "J2") (pin "MP2") (pinfunction "MP2_MP2") (pintype "bidirectional"))
      (node (ref "J2") (pin "MP3") (pinfunction "MP3_MP3") (pintype "bidirectional"))
      (node (ref "J2") (pin "MP4") (pinfunction "MP4_MP4") (pintype "bidirectional"))
      (node (ref "J3") (pin "1") (pinfunction "1_1") (pintype "power_in"))
      (node (ref "J4") (pin "G1") (pinfunction "GND_1_G1") (pintype "bidirectional"))
      (node (ref "J4") (pin "G2") (pinfunction "GND_2_G2") (pintype "bidirectional"))
      (node (ref "J4") (pin "G3") (pinfunction "GND_3_G3") (pintype "bidirectional"))
      (node (ref "J4") (pin "G4") (pinfunction "GND_4_G4") (pintype "bidirectional"))
      (node (ref "J4") (pin "P6") (pinfunction "VSS_P6") (pintype "bidirectional"))
      (node (ref "MCP73831") (pin "2") (pinfunction "VSS_2") (pintype "power_in"))
      (node (ref "R1_PWRUSB") (pin "1") (pinfunction "1_1") (pintype "passive"))
      (node (ref "R2") (pin "1") (pinfunction "1_1") (pintype "passive"))
      (node (ref "R2-USB") (pin "2") (pinfunction "2_2") (pintype "passive"))
      (node (ref "R2-USB1") (pin "1") (pinfunction "1_1") (pintype "passive"))
      (node (ref "R2_BAT") (pin "1") (pinfunction "1_1") (pintype "passive"))
      (node (ref "R4") (pin "1") (pinfunction "1_1") (pintype "passive"))
      (node (ref "RESET_BUTTON") (pin "1") (pinfunction "1_1") (pintype "passive"))
      (node (ref "RESET_BUTTON") (pin "2") (pinfunction "2_2") (pintype "passive"))
      (node (ref "SENSOR2") (pin "1") (pinfunction "GND_1") (pintype "power_in"))
      (node (ref "SENSOR2") (pin "5") (pinfunction "SDO_5") (pintype "bidirectional"))
      (node (ref "SENSOR2") (pin "7") (pinfunction "GND_7") (pintype "power_in"))
      (node (ref "SJ1") (pin "1") (pinfunction "1_1") (pintype "passive"))
      (node (ref "TP4") (pin "TP") (pinfunction "TP_TP") (pintype "input"))
      (node (ref "TP5") (pin "TP") (pinfunction "TP_TP") (pintype "input"))
      (node (ref "U1") (pin "4") (pinfunction "GND_4") (pintype "power_in"))
      (node (ref "U1") (pin "9") (pinfunction "EXP_9") (pintype "passive"))
      (node (ref "U2") (pin "1") (pinfunction "GND_1") (pintype "power_in"))
      (node (ref "U2") (pin "28") (pinfunction "GND_28") (pintype "power_in"))
      (node (ref "U2") (pin "29_1") (pinfunction "GND_29_1") (pintype "power_in"))
      (node (ref "U2") (pin "29_2") (pinfunction "GND_29_2") (pintype "power_in"))
      (node (ref "U2") (pin "29_3") (pinfunction "GND_29_3") (pintype "power_in"))
      (node (ref "U2") (pin "29_4") (pinfunction "GND_29_4") (pintype "power_in"))
      (node (ref "U2") (pin "29_5") (pinfunction "GND_29_5") (pintype "power_in"))
      (node (ref "U2") (pin "29_6") (pinfunction "GND_29_6") (pintype "power_in"))
      (node (ref "U2") (pin "29_7") (pinfunction "GND_29_7") (pintype "power_in"))
      (node (ref "U2") (pin "29_8") (pinfunction "GND_29_8") (pintype "power_in"))
      (node (ref "U2") (pin "29_9") (pinfunction "GND_29_9") (pintype "power_in"))
      (node (ref "U3") (pin "13") (pinfunction "GND_13") (pintype "power_in"))
      (node (ref "U4") (pin "1") (pinfunction "CTG_1") (pintype "power_in"))
      (node (ref "U4") (pin "4") (pinfunction "GND_4") (pintype "power_in"))
      (node (ref "U4") (pin "6") (pinfunction "QSTRT_6") (pintype "input"))
      (node (ref "U4") (pin "9") (pinfunction "EP_9") (pintype "power_in"))
    )
    (net (code "14") (name "GPIO8") (class "Default")
      (node (ref "R1") (pin "1") (pinfunction "1_1") (pintype "passive"))
      (node (ref "U2") (pin "10") (pinfunction "IO8_10") (pintype "bidirectional"))
    )
    (net (code "15") (name "I2C_PW") (class "Default")
      (node (ref "C1") (pin "1") (pinfunction "1_1") (pintype "passive"))
      (node (ref "C2") (pin "1") (pinfunction "1_1") (pintype "passive"))
      (node (ref "R1-PINH") (pin "2") (pinfunction "2_2") (pintype "passive"))
      (node (ref "R2-PINH") (pin "2") (pinfunction "2_2") (pintype "passive"))
      (node (ref "SENSOR2") (pin "2") (pinfunction "CSB_2") (pintype "input"))
      (node (ref "SENSOR2") (pin "6") (pinfunction "VDDIO_6") (pintype "power_in"))
      (node (ref "SENSOR2") (pin "8") (pinfunction "VDD_8") (pintype "power_in"))
      (node (ref "U2") (pin "17") (pinfunction "IO19_17") (pintype "bidirectional"))
    )
    (net (code "16") (name "INT_RTC") (class "Default")
      (node (ref "R1_PINH1") (pin "1") (pinfunction "1_1") (pintype "passive"))
      (node (ref "TP15") (pin "TP") (pinfunction "TP_TP") (pintype "input"))
      (node (ref "U2") (pin "8") (pinfunction "IO0_8") (pintype "bidirectional"))
      (node (ref "U3") (pin "3") (pinfunction "SQW/~{INT}_3") (pintype "output"))
    )
    (net (code "17") (name "IO{slash}BOOT") (class "Default")
      (node (ref "BOOT_BUTTON") (pin "3") (pinfunction "3_3") (pintype "passive"))
      (node (ref "BOOT_BUTTON") (pin "4") (pinfunction "4_4") (pintype "passive"))
      (node (ref "C6") (pin "1") (pinfunction "1_1") (pintype "passive"))
      (node (ref "R_BOOT") (pin "1") (pinfunction "1_1") (pintype "passive"))
      (node (ref "U2") (pin "15") (pinfunction "IO9_15") (pintype "bidirectional"))
    )
    (net (code "18") (name "IO{slash}CHANGE") (class "Default")
      (node (ref "C10") (pin "1") (pinfunction "1_1") (pintype "passive"))
      (node (ref "CHANGE_BUTTON") (pin "3") (pinfunction "3_3") (pintype "passive"))
      (node (ref "CHANGE_BUTTON") (pin "4") (pinfunction "4_4") (pintype "passive"))
      (node (ref "R_CHANGE") (pin "1") (pinfunction "1_1") (pintype "passive"))
      (node (ref "U2") (pin "23") (pinfunction "IO15_23") (pintype "bidirectional"))
    )
    (net (code "19") (name "MISO") (class "Default")
      (node (ref "D12") (pin "2") (pinfunction "2_2") (pintype "passive"))
      (node (ref "J4") (pin "P7") (pinfunction "DAT0_P7") (pintype "bidirectional"))
      (node (ref "R8") (pin "1") (pinfunction "1_1") (pintype "passive"))
      (node (ref "TP6") (pin "TP") (pinfunction "TP_TP") (pintype "input"))
      (node (ref "U1") (pin "2") (pinfunction "DO(IO1)_2") (pintype "bidirectional"))
      (node (ref "U2") (pin "27") (pinfunction "IO2_27") (pintype "bidirectional"))
    )
    (net (code "20") (name "MOSI") (class "Default")
      (node (ref "D11") (pin "2") (pinfunction "2_2") (pintype "passive"))
      (node (ref "J1") (pin "14") (pinfunction "14_14") (pintype "bidirectional"))
      (node (ref "J4") (pin "P3") (pinfunction "CMD_P3") (pintype "bidirectional"))
      (node (ref "R7") (pin "1") (pinfunction "1_1") (pintype "passive"))
      (node (ref "TP7") (pin "TP") (pinfunction "TP_TP") (pintype "input"))
      (node (ref "U1") (pin "5") (pinfunction "DI(IO0)_5") (pintype "bidirectional"))
      (node (ref "U2") (pin "7") (pinfunction "IO7_7") (pintype "bidirectional"))
    )
    (net (code "21") (name "Net-(CHG_LED-PadC)") (class "Default")
      (node (ref "CHG_LED") (pin "C") (pinfunction "C_C") (pintype "passive"))
      (node (ref "R1_BAT") (pin "1") (pinfunction "1_1") (pintype "passive"))
    )
    (net (code "22") (name "Net-(D2-CATHODE)") (class "Default")
      (node (ref "C1_BAT1") (pin "1") (pinfunction "1_1") (pintype "passive"))
      (node (ref "D2") (pin "1") (pinfunction "CATHODE_1") (pintype "bidirectional"))
      (node (ref "IC4") (pin "1") (pinfunction "VIN_1") (pintype "bidirectional"))
      (node (ref "IC4") (pin "3") (pinfunction "CE_3") (pintype "bidirectional"))
      (node (ref "Q1") (pin "2") (pinfunction "S_2") (pintype "bidirectional"))
    )
    (net (code "23") (name "Net-(D3-A)") (class "Default")
      (node (ref "C4") (pin "1") (pinfunction "1_1") (pintype "passive"))
      (node (ref "D3") (pin "2") (pinfunction "A_2") (pintype "bidirectional"))
      (node (ref "D4") (pin "1") (pinfunction "K_1") (pintype "bidirectional"))
    )
    (net (code "24") (name "Net-(D7-CATHODE)") (class "Default")
      (node (ref "D7") (pin "1") (pinfunction "CATHODE_1") (pintype "bidirectional"))
      (node (ref "R_CAPACITOR") (pin "1") (pinfunction "1_1") (pintype "passive"))
    )
    (net (code "25") (name "Net-(EPD_C1-Pad2)") (class "Default")
      (node (ref "EPD_C1") (pin "2") (pinfunction "2_2") (pintype "passive"))
      (node (ref "J1") (pin "4") (pinfunction "4_4") (pintype "bidirectional"))
    )
    (net (code "26") (name "Net-(EPD_C2-Pad2)") (class "Default")
      (node (ref "EPD_C2") (pin "2") (pinfunction "2_2") (pintype "passive"))
      (node (ref "J1") (pin "5") (pinfunction "5_5") (pintype "bidirectional"))
    )
    (net (code "27") (name "Net-(EPD_C6-Pad2)") (class "Default")
      (node (ref "EPD_C6") (pin "2") (pinfunction "2_2") (pintype "passive"))
      (node (ref "J1") (pin "18") (pinfunction "18_18") (pintype "bidirectional"))
    )
    (net (code "28") (name "Net-(EPD_C7-Pad2)") (class "Default")
      (node (ref "EPD_C7") (pin "2") (pinfunction "2_2") (pintype "passive"))
      (node (ref "J1") (pin "19") (pinfunction "19_19") (pintype "bidirectional"))
    )
    (net (code "29") (name "Net-(EPD_C8-Pad2)") (class "Default")
      (node (ref "EPD_C8") (pin "2") (pinfunction "2_2") (pintype "passive"))
      (node (ref "J1") (pin "20") (pinfunction "20_20") (pintype "bidirectional"))
    )
    (net (code "30") (name "Net-(EPD_C10-Pad2)") (class "Default")
      (node (ref "EPD_C10") (pin "2") (pinfunction "2_2") (pintype "passive"))
      (node (ref "J1") (pin "22") (pinfunction "22_22") (pintype "bidirectional"))
    )
    (net (code "31") (name "Net-(EPD_C12-Pad2)") (class "Default")
      (node (ref "EPD_C12") (pin "2") (pinfunction "2_2") (pintype "passive"))
      (node (ref "J1") (pin "24") (pinfunction "24_24") (pintype "bidirectional"))
    )
    (net (code "32") (name "Net-(IC1-CT)") (class "Default")
      (node (ref "C_DELAY") (pin "1") (pinfunction "1_1") (pintype "passive"))
      (node (ref "IC1") (pin "5") (pinfunction "CT_5") (pintype "bidirectional"))
    )
    (net (code "33") (name "Net-(J2-PadA5)") (class "Default")
      (node (ref "J2") (pin "A5") (pinfunction "A5_A5") (pintype "bidirectional"))
      (node (ref "R2-USB1") (pin "2") (pinfunction "2_2") (pintype "passive"))
    )
    (net (code "34") (name "Net-(J2-PadB5)") (class "Default")
      (node (ref "J2") (pin "B5") (pinfunction "B5_B5") (pintype "bidirectional"))
      (node (ref "R2-USB") (pin "1") (pinfunction "1_1") (pintype "passive"))
    )
    (net (code "35") (name "Net-(MCP73831-PROG)") (class "Default")
      (node (ref "MCP73831") (pin "5") (pinfunction "PROG_5") (pintype "input"))
      (node (ref "R2_BAT") (pin "2") (pinfunction "2_2") (pintype "passive"))
    )
    (net (code "36") (name "Net-(MCP73831-STAT)") (class "Default")
      (node (ref "MCP73831") (pin "1") (pinfunction "STAT_1") (pintype "output"))
      (node (ref "R1_BAT") (pin "2") (pinfunction "2_2") (pintype "passive"))
    )
    (net (code "37") (name "PREVGH") (class "Default")
      (node (ref "D5") (pin "1") (pinfunction "K_1") (pintype "bidirectional"))
      (node (ref "EPD_C9") (pin "2") (pinfunction "2_2") (pintype "passive"))
      (node (ref "J1") (pin "21") (pinfunction "21_21") (pintype "bidirectional"))
    )
    (net (code "38") (name "PREVGL") (class "Default")
      (node (ref "D4") (pin "2") (pinfunction "A_2") (pintype "bidirectional"))
      (node (ref "EPD_C11") (pin "2") (pinfunction "2_2") (pintype "passive"))
      (node (ref "J1") (pin "23") (pinfunction "23_23") (pintype "bidirectional"))
    )
    (net (code "39") (name "RESE") (class "Default")
      (node (ref "J1") (pin "3") (pinfunction "3_3") (pintype "bidirectional"))
      (node (ref "Q3") (pin "2") (pinfunction "S_2") (pintype "bidirectional"))
      (node (ref "R3") (pin "2") (pinfunction "2_2") (pintype "passive"))
    )
    (net (code "40") (name "RESE'") (class "Default")
      (node (ref "R2") (pin "2") (pinfunction "2_2") (pintype "passive"))
      (node (ref "R3") (pin "1") (pinfunction "1_1") (pintype "passive"))
      (node (ref "SJ1") (pin "2") (pinfunction "2_2") (pintype "passive"))
    )
    (net (code "41") (name "RESET") (class "Default")
      (node (ref "C5") (pin "1") (pinfunction "1_1") (pintype "passive"))
      (node (ref "IC1") (pin "1") (pinfunction "VOUT_1") (pintype "bidirectional"))
      (node (ref "RESET_BUTTON") (pin "3") (pinfunction "3_3") (pintype "passive"))
      (node (ref "RESET_BUTTON") (pin "4") (pinfunction "4_4") (pintype "passive"))
      (node (ref "R_RESET") (pin "1") (pinfunction "1_1") (pintype "passive"))
      (node (ref "U2") (pin "3") (pinfunction "EN_3") (pintype "input"))
    )
    (net (code "42") (name "RTC_RST") (class "Default")
      (node (ref "U2") (pin "16") (pinfunction "IO18_16") (pintype "bidirectional"))
      (node (ref "U3") (pin "4") (pinfunction "~{RST}_4") (pintype "input"))
    )
    (net (code "43") (name "RX") (class "Default")
      (node (ref "TP2") (pin "TP") (pinfunction "TP_TP") (pintype "input"))
      (node (ref "U2") (pin "24") (pinfunction "RXD0/GPIO17_24") (pintype "bidirectional"))
    )
    (net (code "44") (name "SCK") (class "Default")
      (node (ref "D10") (pin "2") (pinfunction "2_2") (pintype "passive"))
      (node (ref "J1") (pin "13") (pinfunction "13_13") (pintype "bidirectional"))
      (node (ref "J4") (pin "P5") (pinfunction "CLK_P5") (pintype "bidirectional"))
      (node (ref "R6") (pin "1") (pinfunction "1_1") (pintype "passive"))
      (node (ref "TP8") (pin "TP") (pinfunction "TP_TP") (pintype "input"))
      (node (ref "U1") (pin "6") (pinfunction "CLK_6") (pintype "input"))
      (node (ref "U2") (pin "6") (pinfunction "IO6_6") (pintype "bidirectional"))
    )
    (net (code "45") (name "SCL") (class "Default")
      (node (ref "J3") (pin "4") (pinfunction "4_4") (pintype "passive"))
      (node (ref "R2-PINH") (pin "1") (pinfunction "1_1") (pintype "passive"))
      (node (ref "SENSOR2") (pin "4") (pinfunction "SCK_4") (pintype "input"))
      (node (ref "U2") (pin "20") (pinfunction "IO22_20") (pintype "bidirectional"))
      (node (ref "U3") (pin "16") (pinfunction "SCL_16") (pintype "input"))
      (node (ref "U4") (pin "7") (pinfunction "SCL_7") (pintype "input"))
    )
    (net (code "46") (name "SDA") (class "Default")
      (node (ref "J3") (pin "3") (pinfunction "3_3") (pintype "passive"))
      (node (ref "R1-PINH") (pin "1") (pinfunction "1_1") (pintype "passive"))
      (node (ref "SENSOR2") (pin "3") (pinfunction "SDI_3") (pintype "bidirectional"))
      (node (ref "U2") (pin "19") (pinfunction "IO21_19") (pintype "bidirectional"))
      (node (ref "U3") (pin "15") (pinfunction "SDA_15") (pintype "bidirectional"))
      (node (ref "U4") (pin "8") (pinfunction "SDA_8") (pintype "bidirectional"))
    )
    (net (code "47") (name "SRC") (class "Default")
      (node (ref "C4") (pin "2") (pinfunction "2_2") (pintype "passive"))
      (node (ref "D5") (pin "2") (pinfunction "A_2") (pintype "bidirectional"))
      (node (ref "L1") (pin "1") (pinfunction "1_1") (pintype "passive"))
      (node (ref "Q3") (pin "3") (pinfunction "D_3") (pintype "bidirectional"))
    )
    (net (code "48") (name "SS_SD") (class "Default")
      (node (ref "D8") (pin "2") (pinfunction "2_2") (pintype "passive"))
      (node (ref "J4") (pin "P2") (pinfunction "CD/DAT3_P2") (pintype "bidirectional"))
      (node (ref "R10") (pin "1") (pinfunction "1_1") (pintype "passive"))
      (node (ref "U2") (pin "4") (pinfunction "IO4_4") (pintype "bidirectional"))
    )
    (net (code "49") (name "TX") (class "Default")
      (node (ref "TP1") (pin "TP") (pinfunction "TP_TP") (pintype "input"))
      (node (ref "U2") (pin "25") (pinfunction "TXD0/GPIO16_25") (pintype "bidirectional"))
    )
    (net (code "50") (name "USB_D+") (class "Default")
      (node (ref "D1") (pin "1") (pinfunction "I/O1_1_1") (pintype "bidirectional"))
      (node (ref "U2") (pin "14") (pinfunction "IO13_14") (pintype "bidirectional"))
    )
    (net (code "51") (name "USB_D-") (class "Default")
      (node (ref "D1") (pin "3") (pinfunction "I/O2_1_3") (pintype "bidirectional"))
      (node (ref "U2") (pin "13") (pinfunction "IO12_13") (pintype "bidirectional"))
    )
    (net (code "52") (name "VBAT") (class "Default")
      (node (ref "C2_BAT") (pin "1") (pinfunction "1_1") (pintype "passive"))
      (node (ref "MCP73831") (pin "3") (pinfunction "VBAT_3") (pintype "power_in"))
      (node (ref "Q1") (pin "3") (pinfunction "D_3") (pintype "bidirectional"))
      (node (ref "TP3") (pin "TP") (pinfunction "TP_TP") (pintype "input"))
      (node (ref "U4") (pin "2") (pinfunction "CELL_2") (pintype "power_in"))
      (node (ref "U4") (pin "3") (pinfunction "VDD_3") (pintype "power_in"))
    )
    (net (code "53") (name "VBUS") (class "Default")
      (node (ref "C1_BAT") (pin "1") (pinfunction "1_1") (pintype "passive"))
      (node (ref "C4_USB") (pin "1") (pinfunction "1_1") (pintype "passive"))
      (node (ref "C5_USB") (pin "1") (pinfunction "1_1") (pintype "passive"))
      (node (ref "CHG_LED") (pin "A") (pinfunction "A_A") (pintype "passive"))
      (node (ref "D1") (pin "5") (pinfunction "VBUS_5") (pintype "bidirectional"))
      (node (ref "D2") (pin "2") (pinfunction "ANODE_2") (pintype "bidirectional"))
      (node (ref "MCP73831") (pin "4") (pinfunction "VIN_4") (pintype "power_in"))
      (node (ref "PFMF.050.1") (pin "2") (pinfunction "2_2") (pintype "passive"))
      (node (ref "Q1") (pin "1") (pinfunction "G_1") (pintype "bidirectional"))
      (node (ref "R1_PWRUSB") (pin "2") (pinfunction "2_2") (pintype "passive"))
      (node (ref "TP14") (pin "TP") (pinfunction "TP_TP") (pintype "input"))
    )
    (net (code "54") (name "VRTC") (class "Default")
      (node (ref "C10_SUPERCAP") (pin "2") (pinfunction "2_2") (pintype "passive"))
      (node (ref "C8") (pin "1") (pinfunction "1_1") (pintype "passive"))
      (node (ref "R_CAPACITOR") (pin "2") (pinfunction "2_2") (pintype "passive"))
      (node (ref "U3") (pin "14") (pinfunction "VBAT_14") (pintype "power_in"))
    )
    (net (code "55") (name "VUSB") (class "Default")
      (node (ref "J2") (pin "A4") (pinfunction "A4_A4") (pintype "bidirectional"))
      (node (ref "J2") (pin "A9") (pinfunction "A9_A9") (pintype "bidirectional"))
      (node (ref "J2") (pin "B4") (pinfunction "B4_B4") (pintype "bidirectional"))
      (node (ref "J2") (pin "B9") (pinfunction "B9_B9") (pintype "bidirectional"))
      (node (ref "PFMF.050.1") (pin "1") (pinfunction "1_1") (pintype "passive"))
    )
    (net (code "56") (name "unconnected-(IC1-NC-Pad4)") (class "Default")
      (node (ref "IC1") (pin "4") (pinfunction "NC_4") (pintype "no_connect"))
    )
    (net (code "57") (name "unconnected-(IC4-NC-Pad4)") (class "Default")
      (node (ref "IC4") (pin "4") (pinfunction "NC_4") (pintype "no_connect"))
    )
    (net (code "58") (name "unconnected-(J1-Pad1)") (class "Default")
      (node (ref "J1") (pin "1") (pinfunction "1_1") (pintype "bidirectional"))
    )
    (net (code "59") (name "unconnected-(J1-Pad6)") (class "Default")
      (node (ref "J1") (pin "6") (pinfunction "6_6") (pintype "bidirectional"))
    )
    (net (code "60") (name "unconnected-(J1-Pad7)") (class "Default")
      (node (ref "J1") (pin "7") (pinfunction "7_7") (pintype "bidirectional"))
    )
    (net (code "61") (name "unconnected-(J2-PadA8)") (class "Default")
      (node (ref "J2") (pin "A8") (pinfunction "A8_A8") (pintype "bidirectional"))
    )
    (net (code "62") (name "unconnected-(J2-PadB8)") (class "Default")
      (node (ref "J2") (pin "B8") (pinfunction "B8_B8") (pintype "bidirectional"))
    )
    (net (code "63") (name "unconnected-(J4-DAT1-PadP8)") (class "Default")
      (node (ref "J4") (pin "P8") (pinfunction "DAT1_P8") (pintype "bidirectional"))
    )
    (net (code "64") (name "unconnected-(J4-DAT2-PadP1)") (class "Default")
      (node (ref "J4") (pin "P1") (pinfunction "DAT2_P1") (pintype "bidirectional"))
    )
    (net (code "65") (name "unconnected-(J4-DETECTION_1-PadS1)") (class "Default")
      (node (ref "J4") (pin "S1") (pinfunction "DETECTION_1_S1") (pintype "bidirectional"))
    )
    (net (code "66") (name "unconnected-(J4-DETECTION_2-PadS2)") (class "Default")
      (node (ref "J4") (pin "S2") (pinfunction "DETECTION_2_S2") (pintype "bidirectional"))
    )
    (net (code "67") (name "unconnected-(U2-NC-Pad22)") (class "Default")
      (node (ref "U2") (pin "22") (pinfunction "NC_22") (pintype "no_connect"))
    )
    (net (code "68") (name "unconnected-(U4-~{ALERT}-Pad5)") (class "Default")
      (node (ref "U4") (pin "5") (pinfunction "~{ALERT}_5") (pintype "output"))
    )
  )
)
